# POE_PD_4_P-Schalter_minimized.net
KiCad netlist of a schematic drawn in EAGLE
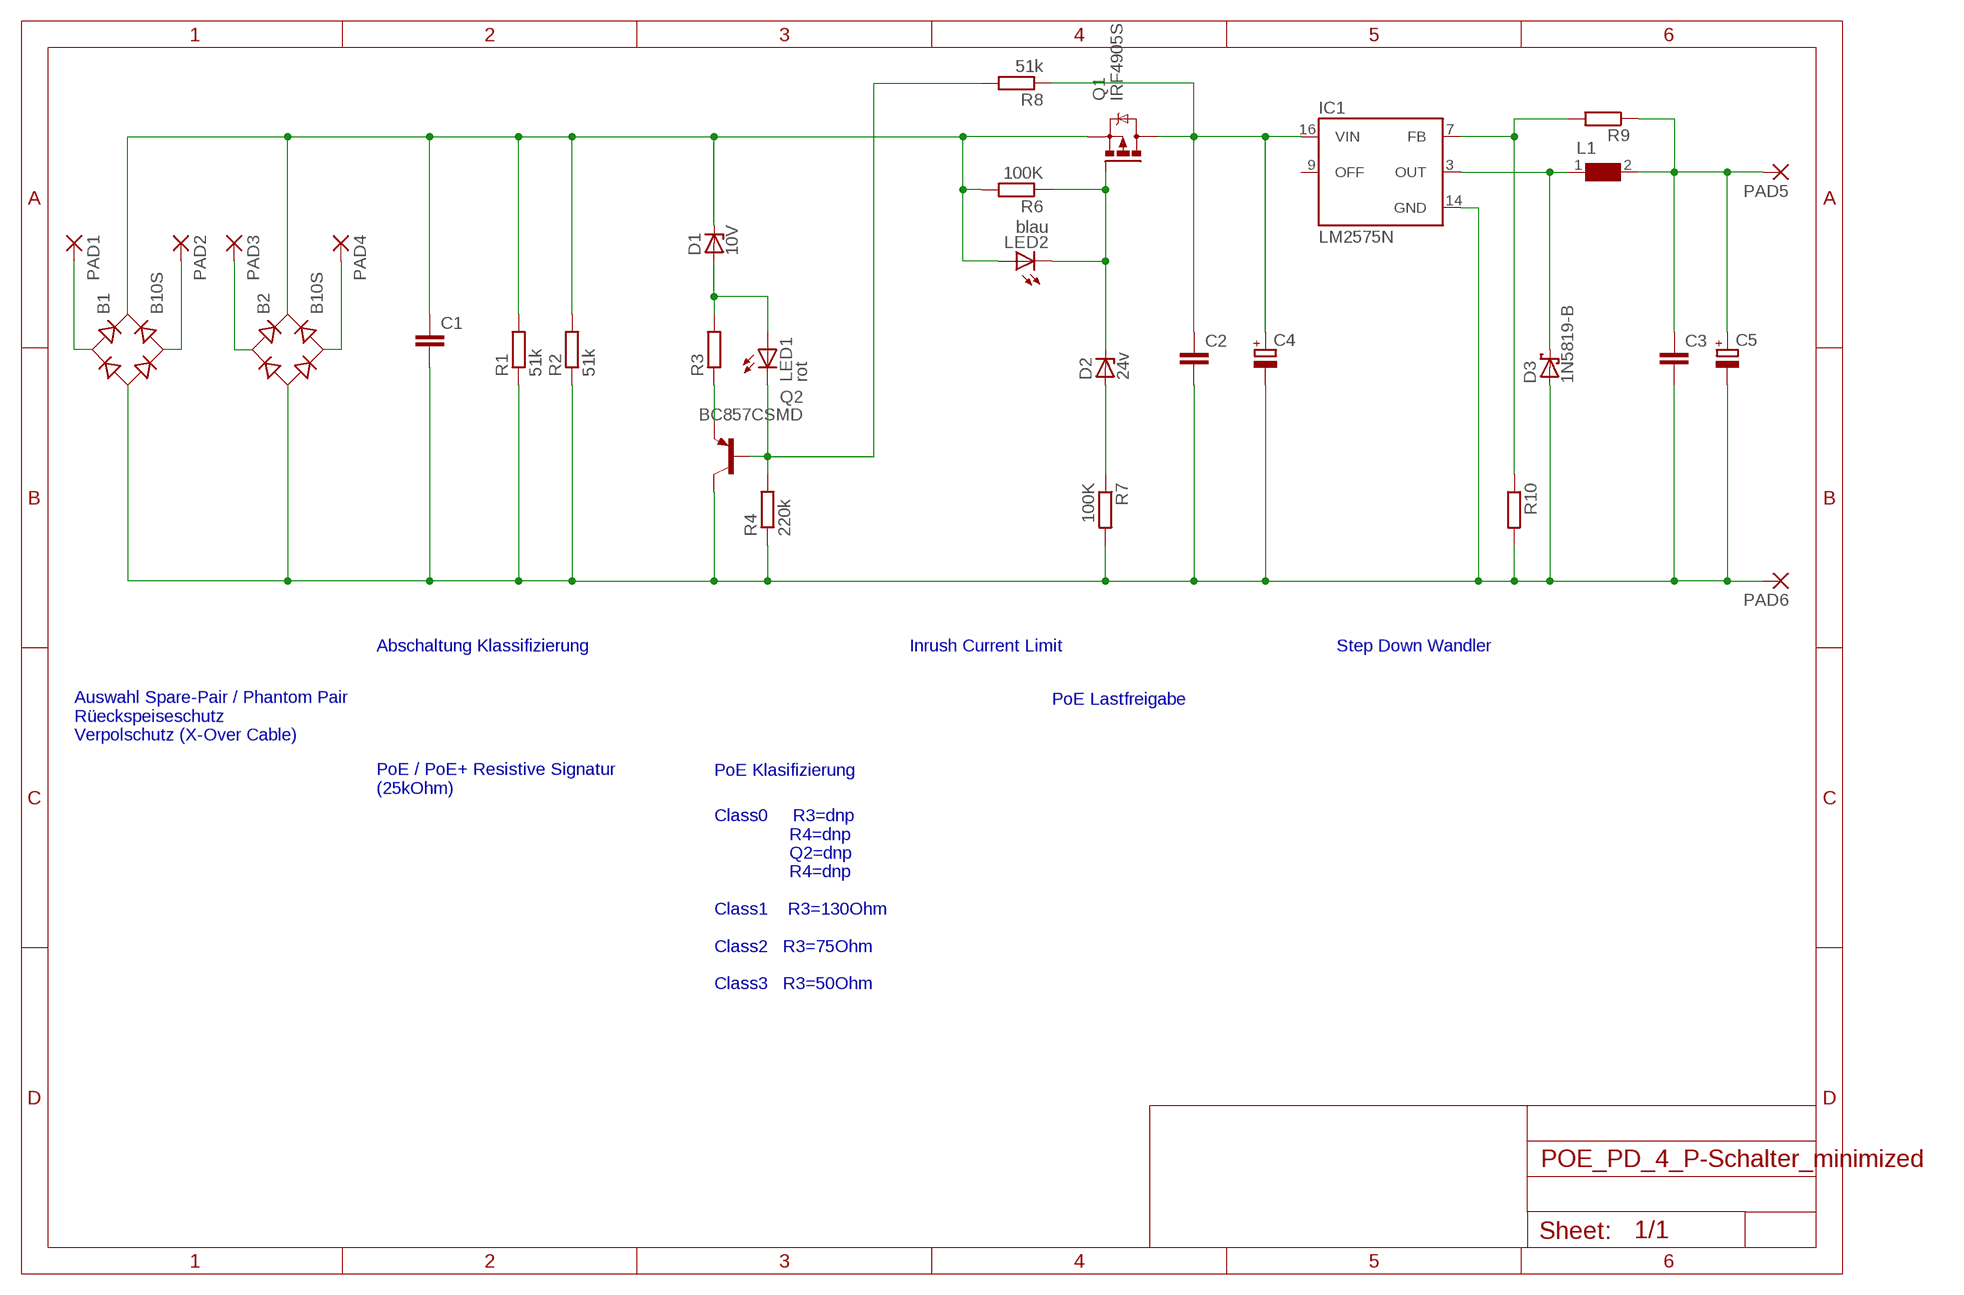
[diagram p0: schematic, sheet 1]

(export (version "E")
  (design (tool "Eeschema 10.0.6"))
  (components
    (comp (ref "B1")
      (value "B10S")
      (footprint "eagle-import:MBS")
      (libsource (lib "eagle-import") (part "BS10"))
    )
    (comp (ref "B2")
      (value "B10S")
      (footprint "eagle-import:MBS")
      (libsource (lib "eagle-import") (part "BS10"))
    )
    (comp (ref "C1")
      (value "C-EUC0805")
      (footprint "eagle-import:C0805")
      (libsource (lib "eagle-import") (part "C-EUC0805"))
    )
    (comp (ref "C2")
      (value "C-EUC0805")
      (footprint "eagle-import:C0805")
      (libsource (lib "eagle-import") (part "C-EUC0805"))
    )
    (comp (ref "C3")
      (value "C-EUC0805")
      (footprint "eagle-import:C0805")
      (libsource (lib "eagle-import") (part "C-EUC0805"))
    )
    (comp (ref "C4")
      (value "CPOL-EUE2.5-5")
      (footprint "eagle-import:E2,5-5")
      (libsource (lib "eagle-import") (part "CPOL-EUE2.5-5"))
    )
    (comp (ref "C5")
      (value "CPOL-EUE2.5-5")
      (footprint "eagle-import:E2,5-5")
      (libsource (lib "eagle-import") (part "CPOL-EUE2.5-5"))
    )
    (comp (ref "D1")
      (value "10V")
      (footprint "eagle-import:SOT23")
      (libsource (lib "eagle-import") (part "ZENER-DIODESOT23"))
    )
    (comp (ref "D2")
      (value "24v")
      (footprint "eagle-import:SOT23")
      (libsource (lib "eagle-import") (part "ZENER-DIODESOT23"))
    )
    (comp (ref "D3")
      (value "1N5819-B")
      (footprint "eagle-import:DO41-7.6")
      (libsource (lib "eagle-import") (part "1N5819-B"))
    )
    (comp (ref "IC1")
      (value "LM2575N")
      (footprint "eagle-import:DIL16")
      (libsource (lib "eagle-import") (part "LM2575N"))
    )
    (comp (ref "L1")
      (value "WE-PD2_S")
      (footprint "eagle-import:WE-PD2_S")
      (libsource (lib "eagle-import") (part "WE-PD2_S"))
    )
    (comp (ref "LED1")
      (value "rot")
      (footprint "eagle-import:CHIP-LED0805")
      (libsource (lib "eagle-import") (part "LEDCHIP-LED0805"))
    )
    (comp (ref "LED2")
      (value "blau")
      (footprint "eagle-import:CHIP-LED0805")
      (libsource (lib "eagle-import") (part "LEDCHIP-LED0805"))
    )
    (comp (ref "PAD1")
      (value "2,15/1,0")
      (footprint "eagle-import:2,15_1,0")
      (libsource (lib "eagle-import") (part "2,15/1,0"))
    )
    (comp (ref "PAD2")
      (value "2,15/1,0")
      (footprint "eagle-import:2,15_1,0")
      (libsource (lib "eagle-import") (part "2,15/1,0"))
    )
    (comp (ref "PAD3")
      (value "2,15/1,0")
      (footprint "eagle-import:2,15_1,0")
      (libsource (lib "eagle-import") (part "2,15/1,0"))
    )
    (comp (ref "PAD4")
      (value "2,15/1,0")
      (footprint "eagle-import:2,15_1,0")
      (libsource (lib "eagle-import") (part "2,15/1,0"))
    )
    (comp (ref "PAD5")
      (value "2,15/1,0")
      (footprint "eagle-import:2,15_1,0")
      (libsource (lib "eagle-import") (part "2,15/1,0"))
    )
    (comp (ref "PAD6")
      (value "2,15/1,0")
      (footprint "eagle-import:2,15_1,0")
      (libsource (lib "eagle-import") (part "2,15/1,0"))
    )
    (comp (ref "Q1")
      (value "IRF4905S")
      (footprint "eagle-import:D-PAK_TO252AA")
      (libsource (lib "eagle-import") (part "IRF?5305R"))
    )
    (comp (ref "Q2")
      (value "BC857CSMD")
      (footprint "eagle-import:SOT23-BEC")
      (libsource (lib "eagle-import") (part "BC857SMDC"))
    )
    (comp (ref "R1")
      (value "51k")
      (footprint "eagle-import:R0603")
      (libsource (lib "eagle-import") (part "R-EU_R0603"))
    )
    (comp (ref "R2")
      (value "51k")
      (footprint "eagle-import:R0603")
      (libsource (lib "eagle-import") (part "R-EU_R0603"))
    )
    (comp (ref "R3")
      (value "R-EU_0207/7")
      (footprint "eagle-import:0207_7")
      (libsource (lib "eagle-import") (part "R-EU_0207/7"))
    )
    (comp (ref "R4")
      (value "220k")
      (footprint "eagle-import:R0603")
      (libsource (lib "eagle-import") (part "R-EU_R0603"))
    )
    (comp (ref "R6")
      (value "100K")
      (footprint "eagle-import:R0603")
      (libsource (lib "eagle-import") (part "R-EU_R0603"))
    )
    (comp (ref "R7")
      (value "100K")
      (footprint "eagle-import:R0603")
      (libsource (lib "eagle-import") (part "R-EU_R0603"))
    )
    (comp (ref "R8")
      (value "51k")
      (footprint "eagle-import:R0603")
      (libsource (lib "eagle-import") (part "R-EU_R0603"))
    )
    (comp (ref "R9")
      (value "R-EU_0207/7")
      (footprint "eagle-import:0207_7")
      (libsource (lib "eagle-import") (part "R-EU_0207/7"))
    )
    (comp (ref "R10")
      (value "R-EU_0207/7")
      (footprint "eagle-import:0207_7")
      (libsource (lib "eagle-import") (part "R-EU_0207/7"))
    )
  )
  (nets
    (net (code "1") (name "Net-(D1-A)") (class "Default")
      (node (ref "D1") (pin "1") (pinfunction "A_1") (pintype "passive"))
      (node (ref "LED1") (pin "A") (pinfunction "A_A") (pintype "passive"))
      (node (ref "R3") (pin "2") (pinfunction "2_2") (pintype "passive"))
    )
    (net (code "2") (name "Net-(D1-C)") (class "Default")
      (node (ref "B1") (pin "+") (pinfunction "+_+") (pintype "passive"))
      (node (ref "B2") (pin "+") (pinfunction "+_+") (pintype "passive"))
      (node (ref "C1") (pin "1") (pinfunction "1_1") (pintype "passive"))
      (node (ref "D1") (pin "3") (pinfunction "C_3") (pintype "passive"))
      (node (ref "LED2") (pin "A") (pinfunction "A_A") (pintype "passive"))
      (node (ref "Q1") (pin "3") (pinfunction "S_3") (pintype "passive"))
      (node (ref "R1") (pin "2") (pinfunction "2_2") (pintype "passive"))
      (node (ref "R2") (pin "2") (pinfunction "2_2") (pintype "passive"))
      (node (ref "R6") (pin "2") (pinfunction "2_2") (pintype "passive"))
    )
    (net (code "3") (name "Net-(D2-A)") (class "Default")
      (node (ref "D2") (pin "1") (pinfunction "A_1") (pintype "passive"))
      (node (ref "R7") (pin "1") (pinfunction "1_1") (pintype "passive"))
    )
    (net (code "4") (name "Net-(D2-C)") (class "Default")
      (node (ref "D2") (pin "3") (pinfunction "C_3") (pintype "passive"))
      (node (ref "LED2") (pin "C") (pinfunction "C_C") (pintype "passive"))
      (node (ref "Q1") (pin "1") (pinfunction "G_1") (pintype "passive"))
      (node (ref "R6") (pin "1") (pinfunction "1_1") (pintype "passive"))
    )
    (net (code "5") (name "Net-(IC1-FB)") (class "Default")
      (node (ref "IC1") (pin "7") (pinfunction "FB_7") (pintype "input"))
      (node (ref "R10") (pin "1") (pinfunction "1_1") (pintype "passive"))
      (node (ref "R9") (pin "2") (pinfunction "2_2") (pintype "passive"))
    )
    (net (code "6") (name "Net-(IC1-GND)") (class "Default")
      (node (ref "B1") (pin "-") (pinfunction "-_-") (pintype "passive"))
      (node (ref "B2") (pin "-") (pinfunction "-_-") (pintype "passive"))
      (node (ref "C1") (pin "2") (pinfunction "2_2") (pintype "passive"))
      (node (ref "C2") (pin "2") (pinfunction "2_2") (pintype "passive"))
      (node (ref "C3") (pin "2") (pinfunction "2_2") (pintype "passive"))
      (node (ref "C4") (pin "-") (pinfunction "-_-") (pintype "passive"))
      (node (ref "C5") (pin "-") (pinfunction "-_-") (pintype "passive"))
      (node (ref "D3") (pin "A") (pinfunction "A_A") (pintype "passive"))
      (node (ref "IC1") (pin "14") (pinfunction "GND_14") (pintype "power_in"))
      (node (ref "PAD6") (pin "1") (pinfunction "P_1") (pintype "passive"))
      (node (ref "Q2") (pin "C") (pinfunction "C_C") (pintype "passive"))
      (node (ref "R1") (pin "1") (pinfunction "1_1") (pintype "passive"))
      (node (ref "R10") (pin "2") (pinfunction "2_2") (pintype "passive"))
      (node (ref "R2") (pin "1") (pinfunction "1_1") (pintype "passive"))
      (node (ref "R4") (pin "1") (pinfunction "1_1") (pintype "passive"))
      (node (ref "R7") (pin "2") (pinfunction "2_2") (pintype "passive"))
    )
    (net (code "7") (name "Net-(IC1-OUT)") (class "Default")
      (node (ref "D3") (pin "C") (pinfunction "C_C") (pintype "passive"))
      (node (ref "IC1") (pin "3") (pinfunction "OUT_3") (pintype "output"))
      (node (ref "L1") (pin "1") (pinfunction "1_1") (pintype "passive"))
    )
    (net (code "8") (name "Net-(IC1-VIN)") (class "Default")
      (node (ref "C2") (pin "1") (pinfunction "1_1") (pintype "passive"))
      (node (ref "C4") (pin "+") (pinfunction "+_+") (pintype "passive"))
      (node (ref "IC1") (pin "16") (pinfunction "VIN_16") (pintype "power_in"))
      (node (ref "Q1") (pin "4") (pinfunction "D_4") (pintype "passive"))
      (node (ref "R8") (pin "1") (pinfunction "1_1") (pintype "passive"))
    )
    (net (code "9") (name "Net-(LED1-PadC)") (class "Default")
      (node (ref "LED1") (pin "C") (pinfunction "C_C") (pintype "passive"))
      (node (ref "Q2") (pin "B") (pinfunction "B_B") (pintype "passive"))
      (node (ref "R4") (pin "2") (pinfunction "2_2") (pintype "passive"))
      (node (ref "R8") (pin "2") (pinfunction "2_2") (pintype "passive"))
    )
    (net (code "10") (name "Net-(PAD1-P)") (class "Default")
      (node (ref "B1") (pin "AC1") (pinfunction "AC1_AC1") (pintype "passive"))
      (node (ref "PAD1") (pin "1") (pinfunction "P_1") (pintype "passive"))
    )
    (net (code "11") (name "Net-(PAD2-P)") (class "Default")
      (node (ref "B1") (pin "AC2") (pinfunction "AC2_AC2") (pintype "passive"))
      (node (ref "PAD2") (pin "1") (pinfunction "P_1") (pintype "passive"))
    )
    (net (code "12") (name "Net-(PAD3-P)") (class "Default")
      (node (ref "B2") (pin "AC1") (pinfunction "AC1_AC1") (pintype "passive"))
      (node (ref "PAD3") (pin "1") (pinfunction "P_1") (pintype "passive"))
    )
    (net (code "13") (name "Net-(PAD4-P)") (class "Default")
      (node (ref "B2") (pin "AC2") (pinfunction "AC2_AC2") (pintype "passive"))
      (node (ref "PAD4") (pin "1") (pinfunction "P_1") (pintype "passive"))
    )
    (net (code "14") (name "Net-(PAD5-P)") (class "Default")
      (node (ref "C3") (pin "1") (pinfunction "1_1") (pintype "passive"))
      (node (ref "C5") (pin "+") (pinfunction "+_+") (pintype "passive"))
      (node (ref "L1") (pin "2") (pinfunction "2_2") (pintype "passive"))
      (node (ref "PAD5") (pin "1") (pinfunction "P_1") (pintype "passive"))
      (node (ref "R9") (pin "1") (pinfunction "1_1") (pintype "passive"))
    )
    (net (code "15") (name "Net-(Q2-PadE)") (class "Default")
      (node (ref "Q2") (pin "E") (pinfunction "E_E") (pintype "passive"))
      (node (ref "R3") (pin "1") (pinfunction "1_1") (pintype "passive"))
    )
    (net (code "16") (name "unconnected-(IC1-OFF-Pad9)") (class "Default")
      (node (ref "IC1") (pin "9") (pinfunction "OFF_9") (pintype "input"))
    )
  )
)
